# Adafruit_0_54_Alphanumeric_v0_1.net
KiCad netlist of a schematic drawn in EAGLE
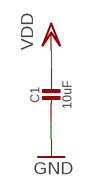
[diagram p0: schematic, sheet 1, part 1 of 2]
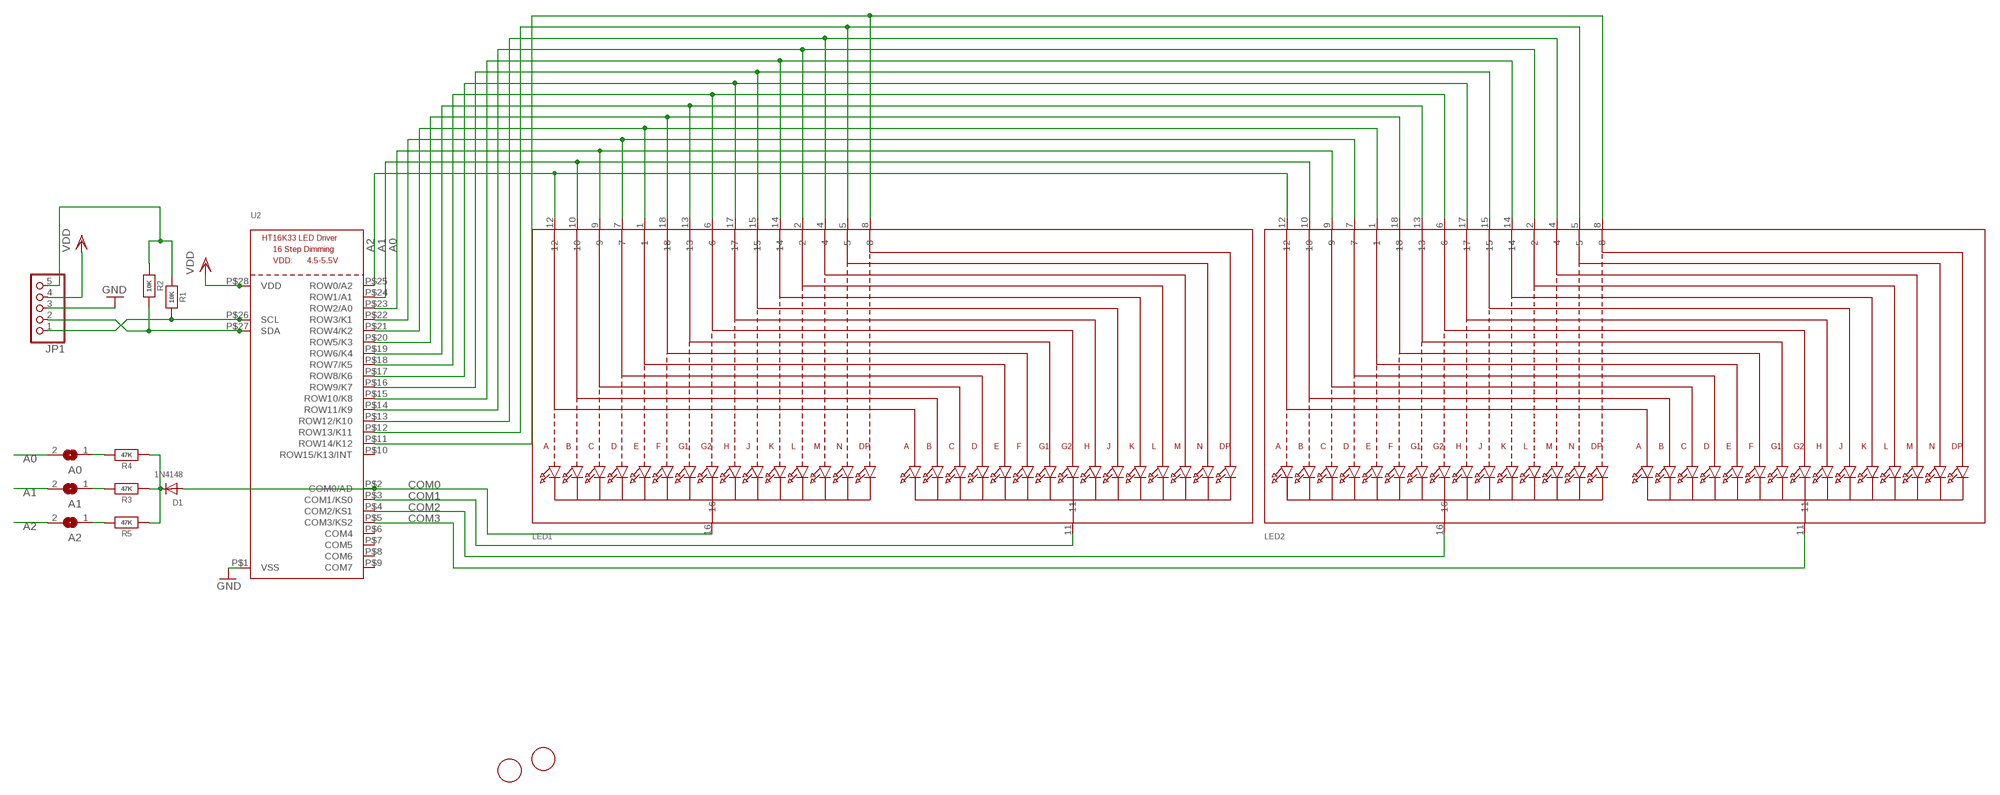
[diagram p1: schematic, sheet 1, part 2 of 2]

(export (version "E")
  (design (tool "Eeschema 10.0.6"))
  (components
    (comp (ref "A0")
      (value "SOLDERJUMPERREFLOW_NOPASTE")
      (footprint "eagle-import:SOLDERJUMPER_REFLOW_NOPASTE")
      (libsource (lib "eagle-import") (part "SOLDERJUMPERREFLOW_NOPASTE"))
    )
    (comp (ref "A1")
      (value "SOLDERJUMPERREFLOW_NOPASTE")
      (footprint "eagle-import:SOLDERJUMPER_REFLOW_NOPASTE")
      (libsource (lib "eagle-import") (part "SOLDERJUMPERREFLOW_NOPASTE"))
    )
    (comp (ref "A2")
      (value "SOLDERJUMPERREFLOW_NOPASTE")
      (footprint "eagle-import:SOLDERJUMPER_REFLOW_NOPASTE")
      (libsource (lib "eagle-import") (part "SOLDERJUMPERREFLOW_NOPASTE"))
    )
    (comp (ref "C1")
      (value "10uF")
      (footprint "eagle-import:0805-NO")
      (libsource (lib "eagle-import") (part "CAP_CERAMIC0805-NOOUTLINE"))
    )
    (comp (ref "D1")
      (value "1N4148")
      (footprint "eagle-import:SOD-323F")
      (libsource (lib "eagle-import") (part "DIODESOD-323F"))
    )
    (comp (ref "JP1")
      (value "HEADER-1X570MIL")
      (footprint "eagle-import:1X05_ROUND_70")
      (libsource (lib "eagle-import") (part "HEADER-1X570MIL"))
    )
    (comp (ref "LED1")
      (value "DISP_SEGMENT_STARBURST_DUAL_COMMONCATHODE")
      (footprint "eagle-import:SEGMENT_STARTBUST_DUAL_KWA-541CBB")
      (libsource (lib "eagle-import") (part "DISP_SEGMENT_STARBURST_DUAL_COMMONCATHODE"))
    )
    (comp (ref "LED2")
      (value "DISP_SEGMENT_STARBURST_DUAL_COMMONCATHODE")
      (footprint "eagle-import:SEGMENT_STARTBUST_DUAL_KWA-541CBB")
      (libsource (lib "eagle-import") (part "DISP_SEGMENT_STARBURST_DUAL_COMMONCATHODE"))
    )
    (comp (ref "R1")
      (value "10K")
      (footprint "eagle-import:0805-NO")
      (libsource (lib "eagle-import") (part "RESISTOR0805_NOOUTLINE"))
    )
    (comp (ref "R2")
      (value "10K")
      (footprint "eagle-import:0805-NO")
      (libsource (lib "eagle-import") (part "RESISTOR0805_NOOUTLINE"))
    )
    (comp (ref "R3")
      (value "47K")
      (footprint "eagle-import:0805-NO")
      (libsource (lib "eagle-import") (part "RESISTOR0805_NOOUTLINE"))
    )
    (comp (ref "R4")
      (value "47K")
      (footprint "eagle-import:0805-NO")
      (libsource (lib "eagle-import") (part "RESISTOR0805_NOOUTLINE"))
    )
    (comp (ref "R5")
      (value "47K")
      (footprint "eagle-import:0805-NO")
      (libsource (lib "eagle-import") (part "RESISTOR0805_NOOUTLINE"))
    )
    (comp (ref "U$1")
      (value "FIDUCIAL")
      (footprint "eagle-import:FIDUCIAL_1MM")
      (libsource (lib "eagle-import") (part "FIDUCIAL"))
    )
    (comp (ref "U$2")
      (value "FIDUCIAL")
      (footprint "eagle-import:FIDUCIAL_1MM")
      (libsource (lib "eagle-import") (part "FIDUCIAL"))
    )
    (comp (ref "U2")
      (value "HT16K33_SOP28")
      (footprint "eagle-import:SOP28_300MIL")
      (libsource (lib "eagle-import") (part "HT16K33_SOP28"))
    )
  )
  (nets
    (net (code "1") (name "/A0") (class "Default")
      (node (ref "A0") (pin "2") (pinfunction "2_2") (pintype "passive"))
      (node (ref "LED1") (pin "9") (pinfunction "9_9") (pintype "bidirectional"))
      (node (ref "LED2") (pin "9") (pinfunction "9_9") (pintype "bidirectional"))
      (node (ref "U2") (pin "P$23") (pinfunction "ROW2/A0_P$23") (pintype "bidirectional"))
    )
    (net (code "2") (name "/A1") (class "Default")
      (node (ref "A1") (pin "2") (pinfunction "2_2") (pintype "passive"))
      (node (ref "LED1") (pin "10") (pinfunction "10_10") (pintype "bidirectional"))
      (node (ref "LED2") (pin "10") (pinfunction "10_10") (pintype "bidirectional"))
      (node (ref "U2") (pin "P$24") (pinfunction "ROW1/A1_P$24") (pintype "bidirectional"))
    )
    (net (code "3") (name "/A2") (class "Default")
      (node (ref "A2") (pin "2") (pinfunction "2_2") (pintype "passive"))
      (node (ref "LED1") (pin "12") (pinfunction "12_12") (pintype "bidirectional"))
      (node (ref "LED2") (pin "12") (pinfunction "12_12") (pintype "bidirectional"))
      (node (ref "U2") (pin "P$25") (pinfunction "ROW0/A2_P$25") (pintype "bidirectional"))
    )
    (net (code "4") (name "/COM0") (class "Default")
      (node (ref "D1") (pin "A") (pinfunction "A_A") (pintype "passive"))
      (node (ref "LED1") (pin "16") (pinfunction "16_16") (pintype "bidirectional"))
      (node (ref "U2") (pin "P$2") (pinfunction "COM0/AD_P$2") (pintype "bidirectional"))
    )
    (net (code "5") (name "/COM1") (class "Default")
      (node (ref "LED1") (pin "11") (pinfunction "11_11") (pintype "bidirectional"))
      (node (ref "U2") (pin "P$3") (pinfunction "COM1/KS0_P$3") (pintype "bidirectional"))
    )
    (net (code "6") (name "/COM2") (class "Default")
      (node (ref "LED2") (pin "16") (pinfunction "16_16") (pintype "bidirectional"))
      (node (ref "U2") (pin "P$4") (pinfunction "COM2/KS1_P$4") (pintype "bidirectional"))
    )
    (net (code "7") (name "/COM3") (class "Default")
      (node (ref "LED2") (pin "11") (pinfunction "11_11") (pintype "bidirectional"))
      (node (ref "U2") (pin "P$5") (pinfunction "COM3/KS2_P$5") (pintype "bidirectional"))
    )
    (net (code "8") (name "GND") (class "Default")
      (node (ref "C1") (pin "2") (pinfunction "2_2") (pintype "passive"))
      (node (ref "JP1") (pin "3") (pinfunction "3_3") (pintype "passive"))
      (node (ref "U2") (pin "P$1") (pinfunction "VSS_P$1") (pintype "bidirectional"))
    )
    (net (code "9") (name "Net-(A0-Pad1)") (class "Default")
      (node (ref "A0") (pin "1") (pinfunction "1_1") (pintype "passive"))
      (node (ref "R4") (pin "2") (pinfunction "2_2") (pintype "passive"))
    )
    (net (code "10") (name "Net-(A1-Pad1)") (class "Default")
      (node (ref "A1") (pin "1") (pinfunction "1_1") (pintype "passive"))
      (node (ref "R3") (pin "2") (pinfunction "2_2") (pintype "passive"))
    )
    (net (code "11") (name "Net-(A2-Pad1)") (class "Default")
      (node (ref "A2") (pin "1") (pinfunction "1_1") (pintype "passive"))
      (node (ref "R5") (pin "2") (pinfunction "2_2") (pintype "passive"))
    )
    (net (code "12") (name "Net-(D1-PadC)") (class "Default")
      (node (ref "D1") (pin "C") (pinfunction "C_C") (pintype "passive"))
      (node (ref "R3") (pin "1") (pinfunction "1_1") (pintype "passive"))
      (node (ref "R4") (pin "1") (pinfunction "1_1") (pintype "passive"))
      (node (ref "R5") (pin "1") (pinfunction "1_1") (pintype "passive"))
    )
    (net (code "13") (name "Net-(JP1-Pad5)") (class "Default")
      (node (ref "JP1") (pin "5") (pinfunction "5_5") (pintype "passive"))
      (node (ref "R1") (pin "1") (pinfunction "1_1") (pintype "passive"))
      (node (ref "R2") (pin "1") (pinfunction "1_1") (pintype "passive"))
    )
    (net (code "14") (name "Net-(U2-ROW3{slash}K1)") (class "Default")
      (node (ref "LED1") (pin "7") (pinfunction "7_7") (pintype "bidirectional"))
      (node (ref "LED2") (pin "7") (pinfunction "7_7") (pintype "bidirectional"))
      (node (ref "U2") (pin "P$22") (pinfunction "ROW3/K1_P$22") (pintype "bidirectional"))
    )
    (net (code "15") (name "Net-(U2-ROW4{slash}K2)") (class "Default")
      (node (ref "LED1") (pin "1") (pinfunction "1_1") (pintype "bidirectional"))
      (node (ref "LED2") (pin "1") (pinfunction "1_1") (pintype "bidirectional"))
      (node (ref "U2") (pin "P$21") (pinfunction "ROW4/K2_P$21") (pintype "bidirectional"))
    )
    (net (code "16") (name "Net-(U2-ROW5{slash}K3)") (class "Default")
      (node (ref "LED1") (pin "18") (pinfunction "18_18") (pintype "bidirectional"))
      (node (ref "LED2") (pin "18") (pinfunction "18_18") (pintype "bidirectional"))
      (node (ref "U2") (pin "P$20") (pinfunction "ROW5/K3_P$20") (pintype "bidirectional"))
    )
    (net (code "17") (name "Net-(U2-ROW6{slash}K4)") (class "Default")
      (node (ref "LED1") (pin "13") (pinfunction "13_13") (pintype "bidirectional"))
      (node (ref "LED2") (pin "13") (pinfunction "13_13") (pintype "bidirectional"))
      (node (ref "U2") (pin "P$19") (pinfunction "ROW6/K4_P$19") (pintype "bidirectional"))
    )
    (net (code "18") (name "Net-(U2-ROW7{slash}K5)") (class "Default")
      (node (ref "LED1") (pin "6") (pinfunction "6_6") (pintype "bidirectional"))
      (node (ref "LED2") (pin "6") (pinfunction "6_6") (pintype "bidirectional"))
      (node (ref "U2") (pin "P$18") (pinfunction "ROW7/K5_P$18") (pintype "bidirectional"))
    )
    (net (code "19") (name "Net-(U2-ROW8{slash}K6)") (class "Default")
      (node (ref "LED1") (pin "17") (pinfunction "17_17") (pintype "bidirectional"))
      (node (ref "LED2") (pin "17") (pinfunction "17_17") (pintype "bidirectional"))
      (node (ref "U2") (pin "P$17") (pinfunction "ROW8/K6_P$17") (pintype "bidirectional"))
    )
    (net (code "20") (name "Net-(U2-ROW9{slash}K7)") (class "Default")
      (node (ref "LED1") (pin "15") (pinfunction "15_15") (pintype "bidirectional"))
      (node (ref "LED2") (pin "15") (pinfunction "15_15") (pintype "bidirectional"))
      (node (ref "U2") (pin "P$16") (pinfunction "ROW9/K7_P$16") (pintype "bidirectional"))
    )
    (net (code "21") (name "Net-(U2-ROW10{slash}K8)") (class "Default")
      (node (ref "LED1") (pin "14") (pinfunction "14_14") (pintype "bidirectional"))
      (node (ref "LED2") (pin "14") (pinfunction "14_14") (pintype "bidirectional"))
      (node (ref "U2") (pin "P$15") (pinfunction "ROW10/K8_P$15") (pintype "bidirectional"))
    )
    (net (code "22") (name "Net-(U2-ROW11{slash}K9)") (class "Default")
      (node (ref "LED1") (pin "2") (pinfunction "2_2") (pintype "bidirectional"))
      (node (ref "LED2") (pin "2") (pinfunction "2_2") (pintype "bidirectional"))
      (node (ref "U2") (pin "P$14") (pinfunction "ROW11/K9_P$14") (pintype "bidirectional"))
    )
    (net (code "23") (name "Net-(U2-ROW12{slash}K10)") (class "Default")
      (node (ref "LED1") (pin "4") (pinfunction "4_4") (pintype "bidirectional"))
      (node (ref "LED2") (pin "4") (pinfunction "4_4") (pintype "bidirectional"))
      (node (ref "U2") (pin "P$13") (pinfunction "ROW12/K10_P$13") (pintype "bidirectional"))
    )
    (net (code "24") (name "Net-(U2-ROW13{slash}K11)") (class "Default")
      (node (ref "LED1") (pin "5") (pinfunction "5_5") (pintype "bidirectional"))
      (node (ref "LED2") (pin "5") (pinfunction "5_5") (pintype "bidirectional"))
      (node (ref "U2") (pin "P$12") (pinfunction "ROW13/K11_P$12") (pintype "bidirectional"))
    )
    (net (code "25") (name "Net-(U2-ROW14{slash}K12)") (class "Default")
      (node (ref "LED1") (pin "8") (pinfunction "8_8") (pintype "bidirectional"))
      (node (ref "LED2") (pin "8") (pinfunction "8_8") (pintype "bidirectional"))
      (node (ref "U2") (pin "P$11") (pinfunction "ROW14/K12_P$11") (pintype "bidirectional"))
    )
    (net (code "26") (name "Net-(U2-SCL)") (class "Default")
      (node (ref "JP1") (pin "1") (pinfunction "1_1") (pintype "passive"))
      (node (ref "R1") (pin "2") (pinfunction "2_2") (pintype "passive"))
      (node (ref "U2") (pin "P$26") (pinfunction "SCL_P$26") (pintype "bidirectional"))
    )
    (net (code "27") (name "Net-(U2-SDA)") (class "Default")
      (node (ref "JP1") (pin "2") (pinfunction "2_2") (pintype "passive"))
      (node (ref "R2") (pin "2") (pinfunction "2_2") (pintype "passive"))
      (node (ref "U2") (pin "P$27") (pinfunction "SDA_P$27") (pintype "bidirectional"))
    )
    (net (code "28") (name "VDD") (class "Default")
      (node (ref "C1") (pin "1") (pinfunction "1_1") (pintype "passive"))
      (node (ref "JP1") (pin "4") (pinfunction "4_4") (pintype "passive"))
      (node (ref "U2") (pin "P$28") (pinfunction "VDD_P$28") (pintype "bidirectional"))
    )
    (net (code "29") (name "unconnected-(U2-COM4-PadP$6)") (class "Default")
      (node (ref "U2") (pin "P$6") (pinfunction "COM4_P$6") (pintype "bidirectional"))
    )
    (net (code "30") (name "unconnected-(U2-COM5-PadP$7)") (class "Default")
      (node (ref "U2") (pin "P$7") (pinfunction "COM5_P$7") (pintype "bidirectional"))
    )
    (net (code "31") (name "unconnected-(U2-COM6-PadP$8)") (class "Default")
      (node (ref "U2") (pin "P$8") (pinfunction "COM6_P$8") (pintype "bidirectional"))
    )
    (net (code "32") (name "unconnected-(U2-COM7-PadP$9)") (class "Default")
      (node (ref "U2") (pin "P$9") (pinfunction "COM7_P$9") (pintype "bidirectional"))
    )
    (net (code "33") (name "unconnected-(U2-ROW15{slash}K13{slash}INT-PadP$10)") (class "Default")
      (node (ref "U2") (pin "P$10") (pinfunction "ROW15/K13/INT_P$10") (pintype "bidirectional"))
    )
  )
)
